# TX5823_ZMR250_V.net
KiCad netlist of a schematic drawn in EAGLE
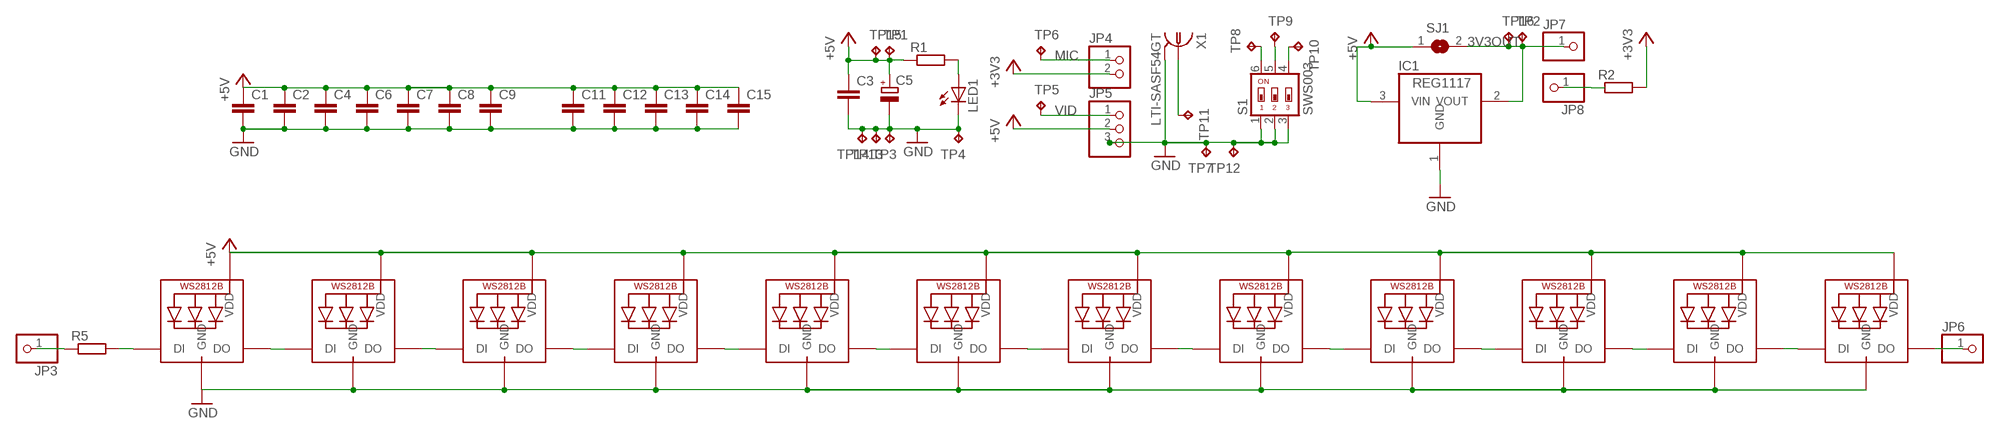
[diagram p0: schematic, sheet 1]

(export (version "E")
  (design (tool "Eeschema 10.0.6"))
  (components
    (comp (ref "C1")
      (value "C-EUC0603")
      (footprint "eagle-import:C0603")
      (libsource (lib "eagle-import") (part "C-EUC0603"))
    )
    (comp (ref "C2")
      (value "C-EUC0603")
      (footprint "eagle-import:C0603")
      (libsource (lib "eagle-import") (part "C-EUC0603"))
    )
    (comp (ref "C3")
      (value "C-EUC0805")
      (footprint "eagle-import:C0805")
      (libsource (lib "eagle-import") (part "C-EUC0805"))
    )
    (comp (ref "C4")
      (value "C-EUC0603")
      (footprint "eagle-import:C0603")
      (libsource (lib "eagle-import") (part "C-EUC0603"))
    )
    (comp (ref "C5")
      (value "CPOL-EUSMCB")
      (footprint "eagle-import:SMC_B")
      (libsource (lib "eagle-import") (part "CPOL-EUSMCB"))
    )
    (comp (ref "C6")
      (value "C-EUC0603")
      (footprint "eagle-import:C0603")
      (libsource (lib "eagle-import") (part "C-EUC0603"))
    )
    (comp (ref "C7")
      (value "C-EUC0603")
      (footprint "eagle-import:C0603")
      (libsource (lib "eagle-import") (part "C-EUC0603"))
    )
    (comp (ref "C8")
      (value "C-EUC0603")
      (footprint "eagle-import:C0603")
      (libsource (lib "eagle-import") (part "C-EUC0603"))
    )
    (comp (ref "C9")
      (value "C-EUC0805")
      (footprint "eagle-import:C0805")
      (libsource (lib "eagle-import") (part "C-EUC0805"))
    )
    (comp (ref "C11")
      (value "C-EUC0603")
      (footprint "eagle-import:C0603")
      (libsource (lib "eagle-import") (part "C-EUC0603"))
    )
    (comp (ref "C12")
      (value "C-EUC0603")
      (footprint "eagle-import:C0603")
      (libsource (lib "eagle-import") (part "C-EUC0603"))
    )
    (comp (ref "C13")
      (value "C-EUC0805")
      (footprint "eagle-import:C0805")
      (libsource (lib "eagle-import") (part "C-EUC0805"))
    )
    (comp (ref "C14")
      (value "C-EUC0805")
      (footprint "eagle-import:C0805")
      (libsource (lib "eagle-import") (part "C-EUC0805"))
    )
    (comp (ref "C15")
      (value "C-EUC0805")
      (footprint "eagle-import:C0805")
      (libsource (lib "eagle-import") (part "C-EUC0805"))
    )
    (comp (ref "IC1")
      (value "REG1117")
      (footprint "eagle-import:SOT223")
      (libsource (lib "eagle-import") (part "REG1117"))
    )
    (comp (ref "JP3")
      (value "PINHD-1X1")
      (footprint "eagle-import:1X01")
      (libsource (lib "eagle-import") (part "PINHD-1X1"))
    )
    (comp (ref "JP4")
      (value "PINHD-1X2")
      (footprint "eagle-import:1X02")
      (libsource (lib "eagle-import") (part "PINHD-1X2"))
    )
    (comp (ref "JP5")
      (value "PINHD-1X3")
      (footprint "eagle-import:1X03")
      (libsource (lib "eagle-import") (part "PINHD-1X3"))
    )
    (comp (ref "JP6")
      (value "PINHD-1X1")
      (footprint "eagle-import:1X01")
      (libsource (lib "eagle-import") (part "PINHD-1X1"))
    )
    (comp (ref "JP7")
      (value "PINHD-1X1")
      (footprint "eagle-import:1X01")
      (libsource (lib "eagle-import") (part "PINHD-1X1"))
    )
    (comp (ref "JP8")
      (value "PINHD-1X1")
      (footprint "eagle-import:1X01")
      (libsource (lib "eagle-import") (part "PINHD-1X1"))
    )
    (comp (ref "LED1")
      (value "LEDCHIPLED_0603")
      (footprint "eagle-import:CHIPLED_0603")
      (libsource (lib "eagle-import") (part "LEDCHIPLED_0603"))
    )
    (comp (ref "LED2")
      (value "WS2812B5050")
      (footprint "eagle-import:WS2812B")
      (libsource (lib "eagle-import") (part "WS2812B5050"))
    )
    (comp (ref "LED3")
      (value "WS2812B5050")
      (footprint "eagle-import:WS2812B")
      (libsource (lib "eagle-import") (part "WS2812B5050"))
    )
    (comp (ref "LED4")
      (value "WS2812B5050")
      (footprint "eagle-import:WS2812B")
      (libsource (lib "eagle-import") (part "WS2812B5050"))
    )
    (comp (ref "LED5")
      (value "WS2812B5050")
      (footprint "eagle-import:WS2812B")
      (libsource (lib "eagle-import") (part "WS2812B5050"))
    )
    (comp (ref "LED6")
      (value "WS2812B5050")
      (footprint "eagle-import:WS2812B")
      (libsource (lib "eagle-import") (part "WS2812B5050"))
    )
    (comp (ref "LED7")
      (value "WS2812B5050")
      (footprint "eagle-import:WS2812B")
      (libsource (lib "eagle-import") (part "WS2812B5050"))
    )
    (comp (ref "LED8")
      (value "WS2812B5050")
      (footprint "eagle-import:WS2812B")
      (libsource (lib "eagle-import") (part "WS2812B5050"))
    )
    (comp (ref "LED9")
      (value "WS2812B5050")
      (footprint "eagle-import:WS2812B")
      (libsource (lib "eagle-import") (part "WS2812B5050"))
    )
    (comp (ref "LED10")
      (value "WS2812B5050")
      (footprint "eagle-import:WS2812B")
      (libsource (lib "eagle-import") (part "WS2812B5050"))
    )
    (comp (ref "LED11")
      (value "WS2812B5050")
      (footprint "eagle-import:WS2812B")
      (libsource (lib "eagle-import") (part "WS2812B5050"))
    )
    (comp (ref "LED12")
      (value "WS2812B5050")
      (footprint "eagle-import:WS2812B")
      (libsource (lib "eagle-import") (part "WS2812B5050"))
    )
    (comp (ref "LED13")
      (value "WS2812B5050")
      (footprint "eagle-import:WS2812B")
      (libsource (lib "eagle-import") (part "WS2812B5050"))
    )
    (comp (ref "R1")
      (value "R-EU_R0603")
      (footprint "eagle-import:R0603")
      (libsource (lib "eagle-import") (part "resistor_R-EU_R0603"))
    )
    (comp (ref "R2")
      (value "R-EU_M1406")
      (footprint "eagle-import:M1406")
      (libsource (lib "eagle-import") (part "R-EU_M1406"))
    )
    (comp (ref "R5")
      (value "R-EU_R0603")
      (footprint "eagle-import:R0603")
      (libsource (lib "eagle-import") (part "resistor_R-EU_R0603"))
    )
    (comp (ref "S1")
      (value "SWS003")
      (footprint "eagle-import:SMS-003")
      (libsource (lib "eagle-import") (part "SWS003"))
    )
    (comp (ref "SJ1") (value "SJ") (footprint "eagle-import:SJ") (libsource (lib "eagle-import") (part "SJ")))
    (comp (ref "TP1")
      (value "TPB1,27")
      (footprint "eagle-import:B1,27")
      (libsource (lib "eagle-import") (part "TPB1,27"))
    )
    (comp (ref "TP2")
      (value "TPB1,27")
      (footprint "eagle-import:B1,27")
      (libsource (lib "eagle-import") (part "TPB1,27"))
    )
    (comp (ref "TP3")
      (value "TPB1,27")
      (footprint "eagle-import:B1,27")
      (libsource (lib "eagle-import") (part "TPB1,27"))
    )
    (comp (ref "TP4")
      (value "TPB1,27")
      (footprint "eagle-import:B1,27")
      (libsource (lib "eagle-import") (part "TPB1,27"))
    )
    (comp (ref "TP5")
      (value "TPB1,27")
      (footprint "eagle-import:B1,27")
      (libsource (lib "eagle-import") (part "TPB1,27"))
    )
    (comp (ref "TP6")
      (value "TPB1,27")
      (footprint "eagle-import:B1,27")
      (libsource (lib "eagle-import") (part "TPB1,27"))
    )
    (comp (ref "TP7")
      (value "TPB1,27")
      (footprint "eagle-import:B1,27")
      (libsource (lib "eagle-import") (part "TPB1,27"))
    )
    (comp (ref "TP8")
      (value "TPB1,27")
      (footprint "eagle-import:B1,27")
      (libsource (lib "eagle-import") (part "TPB1,27"))
    )
    (comp (ref "TP9")
      (value "TPB1,27")
      (footprint "eagle-import:B1,27")
      (libsource (lib "eagle-import") (part "TPB1,27"))
    )
    (comp (ref "TP10")
      (value "TPB1,27")
      (footprint "eagle-import:B1,27")
      (libsource (lib "eagle-import") (part "TPB1,27"))
    )
    (comp (ref "TP11")
      (value "TPB1,27")
      (footprint "eagle-import:B1,27")
      (libsource (lib "eagle-import") (part "TPB1,27"))
    )
    (comp (ref "TP12")
      (value "TPB1,27")
      (footprint "eagle-import:B1,27")
      (libsource (lib "eagle-import") (part "TPB1,27"))
    )
    (comp (ref "TP13")
      (value "TPB1,27")
      (footprint "eagle-import:B1,27")
      (libsource (lib "eagle-import") (part "TPB1,27"))
    )
    (comp (ref "TP14")
      (value "TPB1,27")
      (footprint "eagle-import:B1,27")
      (libsource (lib "eagle-import") (part "TPB1,27"))
    )
    (comp (ref "TP15")
      (value "TPB1,27")
      (footprint "eagle-import:B1,27")
      (libsource (lib "eagle-import") (part "TPB1,27"))
    )
    (comp (ref "TP16")
      (value "TPB1,27")
      (footprint "eagle-import:B1,27")
      (libsource (lib "eagle-import") (part "TPB1,27"))
    )
    (comp (ref "X1")
      (value "LTI-SASF54GT")
      (footprint "eagle-import:LTI-SASF54GT")
      (libsource (lib "eagle-import") (part "LTI-SASF54GT"))
    )
  )
  (nets
    (net (code "1") (name "+3V3") (class "Default")
      (node (ref "JP4") (pin "2") (pinfunction "2_2") (pintype "passive"))
      (node (ref "R2") (pin "2") (pinfunction "2_2") (pintype "passive"))
    )
    (net (code "2") (name "+5V") (class "Default")
      (node (ref "C1") (pin "1") (pinfunction "1_1") (pintype "passive"))
      (node (ref "C11") (pin "1") (pinfunction "1_1") (pintype "passive"))
      (node (ref "C12") (pin "1") (pinfunction "1_1") (pintype "passive"))
      (node (ref "C13") (pin "1") (pinfunction "1_1") (pintype "passive"))
      (node (ref "C14") (pin "1") (pinfunction "1_1") (pintype "passive"))
      (node (ref "C15") (pin "1") (pinfunction "1_1") (pintype "passive"))
      (node (ref "C2") (pin "1") (pinfunction "1_1") (pintype "passive"))
      (node (ref "C3") (pin "1") (pinfunction "1_1") (pintype "passive"))
      (node (ref "C4") (pin "1") (pinfunction "1_1") (pintype "passive"))
      (node (ref "C5") (pin "+") (pinfunction "+_+") (pintype "passive"))
      (node (ref "C6") (pin "1") (pinfunction "1_1") (pintype "passive"))
      (node (ref "C7") (pin "1") (pinfunction "1_1") (pintype "passive"))
      (node (ref "C8") (pin "1") (pinfunction "1_1") (pintype "passive"))
      (node (ref "C9") (pin "1") (pinfunction "1_1") (pintype "passive"))
      (node (ref "IC1") (pin "3") (pinfunction "VIN_3") (pintype "input"))
      (node (ref "JP5") (pin "2") (pinfunction "2_2") (pintype "passive"))
      (node (ref "LED10") (pin "1-VDD") (pinfunction "VDD_1-VDD") (pintype "power_in"))
      (node (ref "LED11") (pin "1-VDD") (pinfunction "VDD_1-VDD") (pintype "power_in"))
      (node (ref "LED12") (pin "1-VDD") (pinfunction "VDD_1-VDD") (pintype "power_in"))
      (node (ref "LED13") (pin "1-VDD") (pinfunction "VDD_1-VDD") (pintype "power_in"))
      (node (ref "LED2") (pin "1-VDD") (pinfunction "VDD_1-VDD") (pintype "power_in"))
      (node (ref "LED3") (pin "1-VDD") (pinfunction "VDD_1-VDD") (pintype "power_in"))
      (node (ref "LED4") (pin "1-VDD") (pinfunction "VDD_1-VDD") (pintype "power_in"))
      (node (ref "LED5") (pin "1-VDD") (pinfunction "VDD_1-VDD") (pintype "power_in"))
      (node (ref "LED6") (pin "1-VDD") (pinfunction "VDD_1-VDD") (pintype "power_in"))
      (node (ref "LED7") (pin "1-VDD") (pinfunction "VDD_1-VDD") (pintype "power_in"))
      (node (ref "LED8") (pin "1-VDD") (pinfunction "VDD_1-VDD") (pintype "power_in"))
      (node (ref "LED9") (pin "1-VDD") (pinfunction "VDD_1-VDD") (pintype "power_in"))
      (node (ref "R1") (pin "1") (pinfunction "1_1") (pintype "passive"))
      (node (ref "SJ1") (pin "1") (pinfunction "1_1") (pintype "passive"))
      (node (ref "TP1") (pin "TP") (pinfunction "TP_TP") (pintype "input"))
      (node (ref "TP15") (pin "TP") (pinfunction "TP_TP") (pintype "input"))
    )
    (net (code "3") (name "/3V3OUT") (class "Default")
      (node (ref "IC1") (pin "2") (pinfunction "VOUT_2") (pintype "output"))
      (node (ref "JP7") (pin "1") (pinfunction "1_1") (pintype "passive"))
      (node (ref "SJ1") (pin "2") (pinfunction "2_2") (pintype "passive"))
      (node (ref "TP16") (pin "TP") (pinfunction "TP_TP") (pintype "input"))
      (node (ref "TP2") (pin "TP") (pinfunction "TP_TP") (pintype "input"))
    )
    (net (code "4") (name "/MIC") (class "Default")
      (node (ref "JP4") (pin "1") (pinfunction "1_1") (pintype "passive"))
      (node (ref "TP6") (pin "TP") (pinfunction "TP_TP") (pintype "input"))
    )
    (net (code "5") (name "/VID") (class "Default")
      (node (ref "JP5") (pin "1") (pinfunction "1_1") (pintype "passive"))
      (node (ref "TP5") (pin "TP") (pinfunction "TP_TP") (pintype "input"))
    )
    (net (code "6") (name "GND") (class "Default")
      (node (ref "C1") (pin "2") (pinfunction "2_2") (pintype "passive"))
      (node (ref "C11") (pin "2") (pinfunction "2_2") (pintype "passive"))
      (node (ref "C12") (pin "2") (pinfunction "2_2") (pintype "passive"))
      (node (ref "C13") (pin "2") (pinfunction "2_2") (pintype "passive"))
      (node (ref "C14") (pin "2") (pinfunction "2_2") (pintype "passive"))
      (node (ref "C15") (pin "2") (pinfunction "2_2") (pintype "passive"))
      (node (ref "C2") (pin "2") (pinfunction "2_2") (pintype "passive"))
      (node (ref "C3") (pin "2") (pinfunction "2_2") (pintype "passive"))
      (node (ref "C4") (pin "2") (pinfunction "2_2") (pintype "passive"))
      (node (ref "C5") (pin "-") (pinfunction "-_-") (pintype "passive"))
      (node (ref "C6") (pin "2") (pinfunction "2_2") (pintype "passive"))
      (node (ref "C7") (pin "2") (pinfunction "2_2") (pintype "passive"))
      (node (ref "C8") (pin "2") (pinfunction "2_2") (pintype "passive"))
      (node (ref "C9") (pin "2") (pinfunction "2_2") (pintype "passive"))
      (node (ref "IC1") (pin "1") (pinfunction "GND_1") (pintype "power_in"))
      (node (ref "JP5") (pin "3") (pinfunction "3_3") (pintype "passive"))
      (node (ref "LED1") (pin "C") (pinfunction "C_C") (pintype "passive"))
      (node (ref "LED10") (pin "3-GND") (pinfunction "GND_3-GND") (pintype "power_in"))
      (node (ref "LED11") (pin "3-GND") (pinfunction "GND_3-GND") (pintype "power_in"))
      (node (ref "LED12") (pin "3-GND") (pinfunction "GND_3-GND") (pintype "power_in"))
      (node (ref "LED13") (pin "3-GND") (pinfunction "GND_3-GND") (pintype "power_in"))
      (node (ref "LED2") (pin "3-GND") (pinfunction "GND_3-GND") (pintype "power_in"))
      (node (ref "LED3") (pin "3-GND") (pinfunction "GND_3-GND") (pintype "power_in"))
      (node (ref "LED4") (pin "3-GND") (pinfunction "GND_3-GND") (pintype "power_in"))
      (node (ref "LED5") (pin "3-GND") (pinfunction "GND_3-GND") (pintype "power_in"))
      (node (ref "LED6") (pin "3-GND") (pinfunction "GND_3-GND") (pintype "power_in"))
      (node (ref "LED7") (pin "3-GND") (pinfunction "GND_3-GND") (pintype "power_in"))
      (node (ref "LED8") (pin "3-GND") (pinfunction "GND_3-GND") (pintype "power_in"))
      (node (ref "LED9") (pin "3-GND") (pinfunction "GND_3-GND") (pintype "power_in"))
      (node (ref "S1") (pin "1") (pinfunction "1_1") (pintype "passive"))
      (node (ref "S1") (pin "2") (pinfunction "2_2") (pintype "passive"))
      (node (ref "S1") (pin "3") (pinfunction "3_3") (pintype "passive"))
      (node (ref "TP12") (pin "TP") (pinfunction "TP_TP") (pintype "input"))
      (node (ref "TP13") (pin "TP") (pinfunction "TP_TP") (pintype "input"))
      (node (ref "TP14") (pin "TP") (pinfunction "TP_TP") (pintype "input"))
      (node (ref "TP3") (pin "TP") (pinfunction "TP_TP") (pintype "input"))
      (node (ref "TP4") (pin "TP") (pinfunction "TP_TP") (pintype "input"))
      (node (ref "TP7") (pin "TP") (pinfunction "TP_TP") (pintype "input"))
      (node (ref "X1") (pin "2") (pinfunction "2_2") (pintype "passive"))
      (node (ref "X1") (pin "3") (pinfunction "2_3") (pintype "passive"))
      (node (ref "X1") (pin "4") (pinfunction "2_4") (pintype "passive"))
      (node (ref "X1") (pin "5") (pinfunction "2_5") (pintype "passive"))
    )
    (net (code "7") (name "Net-(JP3-Pad1)") (class "Default")
      (node (ref "JP3") (pin "1") (pinfunction "1_1") (pintype "passive"))
      (node (ref "R5") (pin "1") (pinfunction "1_1") (pintype "passive"))
    )
    (net (code "8") (name "Net-(JP8-Pad1)") (class "Default")
      (node (ref "JP8") (pin "1") (pinfunction "1_1") (pintype "passive"))
      (node (ref "R2") (pin "1") (pinfunction "1_1") (pintype "passive"))
    )
    (net (code "9") (name "Net-(LED1-PadA)") (class "Default")
      (node (ref "LED1") (pin "A") (pinfunction "A_A") (pintype "passive"))
      (node (ref "R1") (pin "2") (pinfunction "2_2") (pintype "passive"))
    )
    (net (code "10") (name "Net-(LED2-DI)") (class "Default")
      (node (ref "LED2") (pin "4-DIN") (pinfunction "DI_4-DIN") (pintype "input"))
      (node (ref "R5") (pin "2") (pinfunction "2_2") (pintype "passive"))
    )
    (net (code "11") (name "Net-(LED2-DO)") (class "Default")
      (node (ref "LED2") (pin "2-DOUT") (pinfunction "DO_2-DOUT") (pintype "output"))
      (node (ref "LED3") (pin "4-DIN") (pinfunction "DI_4-DIN") (pintype "input"))
    )
    (net (code "12") (name "Net-(LED3-DO)") (class "Default")
      (node (ref "LED3") (pin "2-DOUT") (pinfunction "DO_2-DOUT") (pintype "output"))
      (node (ref "LED4") (pin "4-DIN") (pinfunction "DI_4-DIN") (pintype "input"))
    )
    (net (code "13") (name "Net-(LED4-DO)") (class "Default")
      (node (ref "LED4") (pin "2-DOUT") (pinfunction "DO_2-DOUT") (pintype "output"))
      (node (ref "LED5") (pin "4-DIN") (pinfunction "DI_4-DIN") (pintype "input"))
    )
    (net (code "14") (name "Net-(LED5-DO)") (class "Default")
      (node (ref "LED5") (pin "2-DOUT") (pinfunction "DO_2-DOUT") (pintype "output"))
      (node (ref "LED6") (pin "4-DIN") (pinfunction "DI_4-DIN") (pintype "input"))
    )
    (net (code "15") (name "Net-(LED6-DO)") (class "Default")
      (node (ref "LED6") (pin "2-DOUT") (pinfunction "DO_2-DOUT") (pintype "output"))
      (node (ref "LED7") (pin "4-DIN") (pinfunction "DI_4-DIN") (pintype "input"))
    )
    (net (code "16") (name "Net-(LED7-DO)") (class "Default")
      (node (ref "LED7") (pin "2-DOUT") (pinfunction "DO_2-DOUT") (pintype "output"))
      (node (ref "LED9") (pin "4-DIN") (pinfunction "DI_4-DIN") (pintype "input"))
    )
    (net (code "17") (name "Net-(LED10-DI)") (class "Default")
      (node (ref "LED10") (pin "4-DIN") (pinfunction "DI_4-DIN") (pintype "input"))
      (node (ref "LED9") (pin "2-DOUT") (pinfunction "DO_2-DOUT") (pintype "output"))
    )
    (net (code "18") (name "Net-(LED10-DO)") (class "Default")
      (node (ref "LED10") (pin "2-DOUT") (pinfunction "DO_2-DOUT") (pintype "output"))
      (node (ref "LED8") (pin "4-DIN") (pinfunction "DI_4-DIN") (pintype "input"))
    )
    (net (code "19") (name "Net-(LED11-DI)") (class "Default")
      (node (ref "LED11") (pin "4-DIN") (pinfunction "DI_4-DIN") (pintype "input"))
      (node (ref "LED8") (pin "2-DOUT") (pinfunction "DO_2-DOUT") (pintype "output"))
    )
    (net (code "20") (name "Net-(LED11-DO)") (class "Default")
      (node (ref "LED11") (pin "2-DOUT") (pinfunction "DO_2-DOUT") (pintype "output"))
      (node (ref "LED12") (pin "4-DIN") (pinfunction "DI_4-DIN") (pintype "input"))
    )
    (net (code "21") (name "Net-(LED12-DO)") (class "Default")
      (node (ref "LED12") (pin "2-DOUT") (pinfunction "DO_2-DOUT") (pintype "output"))
      (node (ref "LED13") (pin "4-DIN") (pinfunction "DI_4-DIN") (pintype "input"))
    )
    (net (code "22") (name "Net-(LED13-DO)") (class "Default")
      (node (ref "JP6") (pin "1") (pinfunction "1_1") (pintype "passive"))
      (node (ref "LED13") (pin "2-DOUT") (pinfunction "DO_2-DOUT") (pintype "output"))
    )
    (net (code "23") (name "Net-(S1-Pad4)") (class "Default")
      (node (ref "S1") (pin "4") (pinfunction "4_4") (pintype "passive"))
      (node (ref "TP10") (pin "TP") (pinfunction "TP_TP") (pintype "input"))
    )
    (net (code "24") (name "Net-(S1-Pad5)") (class "Default")
      (node (ref "S1") (pin "5") (pinfunction "5_5") (pintype "passive"))
      (node (ref "TP9") (pin "TP") (pinfunction "TP_TP") (pintype "input"))
    )
    (net (code "25") (name "Net-(S1-Pad6)") (class "Default")
      (node (ref "S1") (pin "6") (pinfunction "6_6") (pintype "passive"))
      (node (ref "TP8") (pin "TP") (pinfunction "TP_TP") (pintype "input"))
    )
    (net (code "26") (name "Net-(TP11-PadTP)") (class "Default")
      (node (ref "TP11") (pin "TP") (pinfunction "TP_TP") (pintype "input"))
      (node (ref "X1") (pin "1") (pinfunction "1_1") (pintype "passive"))
    )
  )
)
